# 20_FPGA_Power.net
KiCad netlist of a schematic drawn in Altium Designer
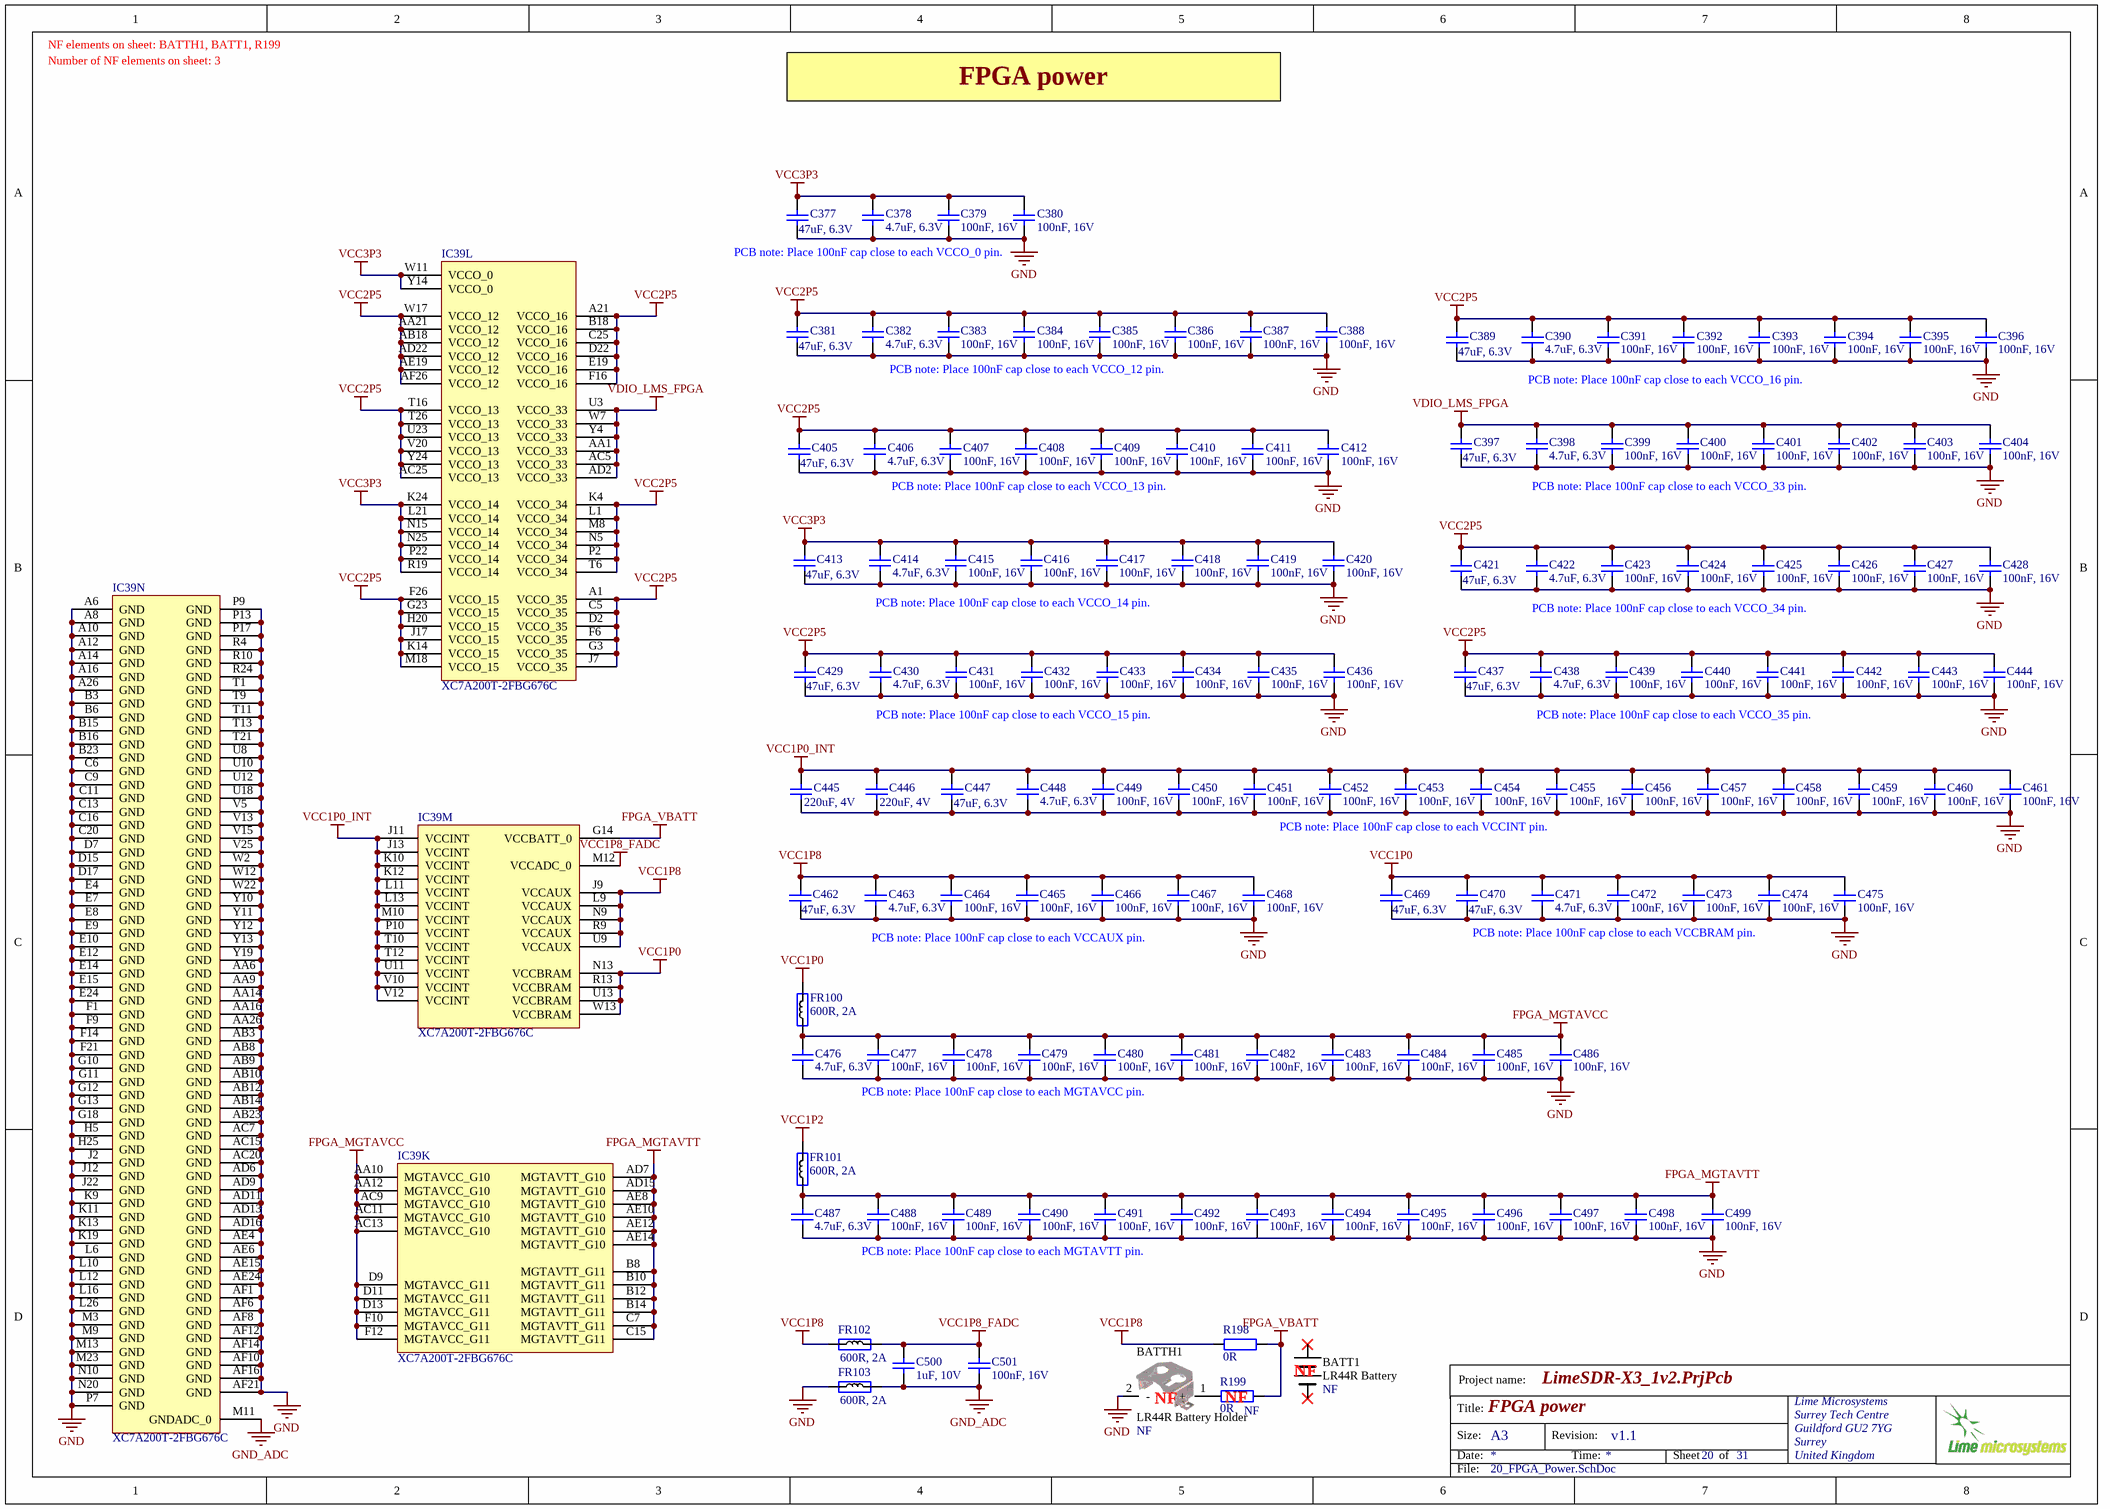
[diagram p0: 20_FPGA_Power.SchDoc]

(export (version "E")
  (design (tool "Eeschema 10.0.6"))
  (components
    (comp (ref "BATT1")
      (value "LR44R Battery")
      (fields (field (name "MANUFACTURER") "Murata") (field (name "ASSEMBLY INFO") "NF"))
      (libsource (lib "LimeMicroAltiumLib_schLib_r03") (part "LR44R_BATTERY"))
    )
    (comp (ref "BATTH1")
      (value "LR44R Battery Holder")
      (footprint "LR44R_BATTERY_HOLDER")
      (fields (field (name "MANUFACTURER") "Keystone Electronics") (field (name "ASSEMBLY INFO") "NF"))
      (libsource (lib "LimeMicroAltiumLib_schLib_r04") (part "LR44R_BATTERY_HOLDER"))
    )
    (comp (ref "C377")
      (value "47uF, 6.3V")
      (footprint "CAP1206")
      (fields
        (field (name "TOLERANCE") "±20%")
        (field (name "MANUFACTURER") "Samsung Electro-Mechanics")
        (field (name "MANUFACTURER PART NUMBER") "CL31A476MQHNNNE")
      )
      (libsource (lib "") (part "Cap_1206_1"))
    )
    (comp (ref "C378")
      (value "4.7uF, 6.3V")
      (footprint "CAP0402")
      (fields
        (field (name "MANUFACTURER") "Murata Electronics North America")
        (field (name "TOLERANCE") "±20%")
      )
      (libsource (lib "LimeMicroAltiumLib_schLib") (part "Cap_0402"))
    )
    (comp (ref "C379")
      (value "100nF, 16V")
      (footprint "CAP0402")
      (fields (field (name "MANUFACTURER") "Murata Electronics") (field (name "TOLERANCE") "10 %"))
      (libsource (lib "LimeMicroAltiumLib_schLib") (part "Cap_0402"))
    )
    (comp (ref "C380")
      (value "100nF, 16V")
      (footprint "CAP0402")
      (fields (field (name "MANUFACTURER") "Murata Electronics") (field (name "TOLERANCE") "10 %"))
      (libsource (lib "LimeMicroAltiumLib_schLib") (part "Cap_0402"))
    )
    (comp (ref "C381")
      (value "47uF, 6.3V")
      (footprint "CAP1206")
      (fields
        (field (name "TOLERANCE") "±20%")
        (field (name "MANUFACTURER") "Samsung Electro-Mechanics")
        (field (name "MANUFACTURER PART NUMBER") "CL31A476MQHNNNE")
      )
      (libsource (lib "") (part "Cap_1206_1"))
    )
    (comp (ref "C382")
      (value "4.7uF, 6.3V")
      (footprint "CAP0402")
      (fields
        (field (name "MANUFACTURER") "Murata Electronics North America")
        (field (name "TOLERANCE") "±20%")
      )
      (libsource (lib "LimeMicroAltiumLib_schLib") (part "Cap_0402"))
    )
    (comp (ref "C383")
      (value "100nF, 16V")
      (footprint "CAP0402")
      (fields (field (name "MANUFACTURER") "Murata Electronics") (field (name "TOLERANCE") "10 %"))
      (libsource (lib "LimeMicroAltiumLib_schLib") (part "Cap_0402"))
    )
    (comp (ref "C384")
      (value "100nF, 16V")
      (footprint "CAP0402")
      (fields (field (name "MANUFACTURER") "Murata Electronics") (field (name "TOLERANCE") "10 %"))
      (libsource (lib "LimeMicroAltiumLib_schLib") (part "Cap_0402"))
    )
    (comp (ref "C385")
      (value "100nF, 16V")
      (footprint "CAP0402")
      (fields (field (name "MANUFACTURER") "Murata Electronics") (field (name "TOLERANCE") "10 %"))
      (libsource (lib "") (part "Cap_0402_1"))
    )
    (comp (ref "C386")
      (value "100nF, 16V")
      (footprint "CAP0402")
      (fields (field (name "MANUFACTURER") "Murata Electronics") (field (name "TOLERANCE") "10 %"))
      (libsource (lib "") (part "Cap_0402_2"))
    )
    (comp (ref "C387")
      (value "100nF, 16V")
      (footprint "CAP0402")
      (fields (field (name "MANUFACTURER") "Murata Electronics") (field (name "TOLERANCE") "10 %"))
      (libsource (lib "") (part "Cap_0402_2"))
    )
    (comp (ref "C388")
      (value "100nF, 16V")
      (footprint "CAP0402")
      (fields (field (name "MANUFACTURER") "Murata Electronics") (field (name "TOLERANCE") "10 %"))
      (libsource (lib "LimeMicroAltiumLib_schLib") (part "Cap_0402"))
    )
    (comp (ref "C389")
      (value "47uF, 6.3V")
      (footprint "CAP1206")
      (fields
        (field (name "TOLERANCE") "±20%")
        (field (name "MANUFACTURER") "Samsung Electro-Mechanics")
        (field (name "MANUFACTURER PART NUMBER") "CL31A476MQHNNNE")
      )
      (libsource (lib "") (part "Cap_1206_1"))
    )
    (comp (ref "C390")
      (value "4.7uF, 6.3V")
      (footprint "CAP0402")
      (fields
        (field (name "MANUFACTURER") "Murata Electronics North America")
        (field (name "TOLERANCE") "±20%")
      )
      (libsource (lib "LimeMicroAltiumLib_schLib") (part "Cap_0402"))
    )
    (comp (ref "C391")
      (value "100nF, 16V")
      (footprint "CAP0402")
      (fields (field (name "MANUFACTURER") "Murata Electronics") (field (name "TOLERANCE") "10 %"))
      (libsource (lib "LimeMicroAltiumLib_schLib") (part "Cap_0402"))
    )
    (comp (ref "C392")
      (value "100nF, 16V")
      (footprint "CAP0402")
      (fields (field (name "MANUFACTURER") "Murata Electronics") (field (name "TOLERANCE") "10 %"))
      (libsource (lib "LimeMicroAltiumLib_schLib") (part "Cap_0402"))
    )
    (comp (ref "C393")
      (value "100nF, 16V")
      (footprint "CAP0402")
      (fields (field (name "MANUFACTURER") "Murata Electronics") (field (name "TOLERANCE") "10 %"))
      (libsource (lib "") (part "Cap_0402_1"))
    )
    (comp (ref "C394")
      (value "100nF, 16V")
      (footprint "CAP0402")
      (fields (field (name "MANUFACTURER") "Murata Electronics") (field (name "TOLERANCE") "10 %"))
      (libsource (lib "") (part "Cap_0402_2"))
    )
    (comp (ref "C395")
      (value "100nF, 16V")
      (footprint "CAP0402")
      (fields (field (name "MANUFACTURER") "Murata Electronics") (field (name "TOLERANCE") "10 %"))
      (libsource (lib "") (part "Cap_0402_2"))
    )
    (comp (ref "C396")
      (value "100nF, 16V")
      (footprint "CAP0402")
      (fields (field (name "MANUFACTURER") "Murata Electronics") (field (name "TOLERANCE") "10 %"))
      (libsource (lib "LimeMicroAltiumLib_schLib") (part "Cap_0402"))
    )
    (comp (ref "C397")
      (value "47uF, 6.3V")
      (footprint "CAP1206")
      (fields
        (field (name "TOLERANCE") "±20%")
        (field (name "MANUFACTURER") "Samsung Electro-Mechanics")
        (field (name "MANUFACTURER PART NUMBER") "CL31A476MQHNNNE")
      )
      (libsource (lib "LimeFPGAboard_schLib") (part "Cap_1206"))
    )
    (comp (ref "C398")
      (value "4.7uF, 6.3V")
      (footprint "CAP0402")
      (fields
        (field (name "MANUFACTURER") "Murata Electronics North America")
        (field (name "TOLERANCE") "±20%")
      )
      (libsource (lib "LimeMicroAltiumLib_schLib") (part "Cap_0402"))
    )
    (comp (ref "C399")
      (value "100nF, 16V")
      (footprint "CAP0402")
      (fields (field (name "MANUFACTURER") "Murata Electronics") (field (name "TOLERANCE") "10 %"))
      (libsource (lib "") (part "Cap_0402_2"))
    )
    (comp (ref "C400")
      (value "100nF, 16V")
      (footprint "CAP0402")
      (fields (field (name "MANUFACTURER") "Murata Electronics") (field (name "TOLERANCE") "10 %"))
      (libsource (lib "LimeMicroAltiumLib_schLib") (part "Cap_0402"))
    )
    (comp (ref "C401")
      (value "100nF, 16V")
      (footprint "CAP0402")
      (fields (field (name "MANUFACTURER") "Murata Electronics") (field (name "TOLERANCE") "10 %"))
      (libsource (lib "LimeMicroAltiumLib_schLib") (part "Cap_0402"))
    )
    (comp (ref "C402")
      (value "100nF, 16V")
      (footprint "CAP0402")
      (fields (field (name "MANUFACTURER") "Murata Electronics") (field (name "TOLERANCE") "10 %"))
      (libsource (lib "") (part "Cap_0402_1"))
    )
    (comp (ref "C403")
      (value "100nF, 16V")
      (footprint "CAP0402")
      (fields (field (name "MANUFACTURER") "Murata Electronics") (field (name "TOLERANCE") "10 %"))
      (libsource (lib "") (part "Cap_0402_2"))
    )
    (comp (ref "C404")
      (value "100nF, 16V")
      (footprint "CAP0402")
      (fields (field (name "MANUFACTURER") "Murata Electronics") (field (name "TOLERANCE") "10 %"))
      (libsource (lib "") (part "Cap_0402_2"))
    )
    (comp (ref "C405")
      (value "47uF, 6.3V")
      (footprint "CAP1206")
      (fields
        (field (name "TOLERANCE") "±20%")
        (field (name "MANUFACTURER") "Samsung Electro-Mechanics")
        (field (name "MANUFACTURER PART NUMBER") "CL31A476MQHNNNE")
      )
      (libsource (lib "") (part "Cap_1206_2"))
    )
    (comp (ref "C406")
      (value "4.7uF, 6.3V")
      (footprint "CAP0402")
      (fields
        (field (name "MANUFACTURER") "Murata Electronics North America")
        (field (name "TOLERANCE") "±20%")
      )
      (libsource (lib "") (part "Cap_0402_2"))
    )
    (comp (ref "C407")
      (value "100nF, 16V")
      (footprint "CAP0402")
      (fields (field (name "MANUFACTURER") "Murata Electronics") (field (name "TOLERANCE") "10 %"))
      (libsource (lib "") (part "Cap_0402_1"))
    )
    (comp (ref "C408")
      (value "100nF, 16V")
      (footprint "CAP0402")
      (fields (field (name "MANUFACTURER") "Murata Electronics") (field (name "TOLERANCE") "10 %"))
      (libsource (lib "") (part "Cap_0402_2"))
    )
    (comp (ref "C409")
      (value "100nF, 16V")
      (footprint "CAP0402")
      (fields (field (name "MANUFACTURER") "Murata Electronics") (field (name "TOLERANCE") "10 %"))
      (libsource (lib "") (part "Cap_0402_2"))
    )
    (comp (ref "C410")
      (value "100nF, 16V")
      (footprint "CAP0402")
      (fields (field (name "MANUFACTURER") "Murata Electronics") (field (name "TOLERANCE") "10 %"))
      (libsource (lib "LimeMicroAltiumLib_schLib") (part "Cap_0402"))
    )
    (comp (ref "C411")
      (value "100nF, 16V")
      (footprint "CAP0402")
      (fields (field (name "MANUFACTURER") "Murata Electronics") (field (name "TOLERANCE") "10 %"))
      (libsource (lib "LimeMicroAltiumLib_schLib") (part "Cap_0402"))
    )
    (comp (ref "C412")
      (value "100nF, 16V")
      (footprint "CAP0402")
      (fields (field (name "MANUFACTURER") "Murata Electronics") (field (name "TOLERANCE") "10 %"))
      (libsource (lib "") (part "Cap_0402_1"))
    )
    (comp (ref "C413")
      (value "47uF, 6.3V")
      (footprint "CAP1206")
      (fields
        (field (name "TOLERANCE") "±20%")
        (field (name "MANUFACTURER") "Samsung Electro-Mechanics")
        (field (name "MANUFACTURER PART NUMBER") "CL31A476MQHNNNE")
      )
      (libsource (lib "") (part "Cap_1206_2"))
    )
    (comp (ref "C414")
      (value "4.7uF, 6.3V")
      (footprint "CAP0402")
      (fields
        (field (name "MANUFACTURER") "Murata Electronics North America")
        (field (name "TOLERANCE") "±20%")
      )
      (libsource (lib "") (part "Cap_0402_2"))
    )
    (comp (ref "C415")
      (value "100nF, 16V")
      (footprint "CAP0402")
      (fields (field (name "MANUFACTURER") "Murata Electronics") (field (name "TOLERANCE") "10 %"))
      (libsource (lib "") (part "Cap_0402_1"))
    )
    (comp (ref "C416")
      (value "100nF, 16V")
      (footprint "CAP0402")
      (fields (field (name "MANUFACTURER") "Murata Electronics") (field (name "TOLERANCE") "10 %"))
      (libsource (lib "") (part "Cap_0402_2"))
    )
    (comp (ref "C417")
      (value "100nF, 16V")
      (footprint "CAP0402")
      (fields (field (name "MANUFACTURER") "Murata Electronics") (field (name "TOLERANCE") "10 %"))
      (libsource (lib "") (part "Cap_0402_2"))
    )
    (comp (ref "C418")
      (value "100nF, 16V")
      (footprint "CAP0402")
      (fields (field (name "MANUFACTURER") "Murata Electronics") (field (name "TOLERANCE") "10 %"))
      (libsource (lib "LimeMicroAltiumLib_schLib") (part "Cap_0402"))
    )
    (comp (ref "C419")
      (value "100nF, 16V")
      (footprint "CAP0402")
      (fields (field (name "MANUFACTURER") "Murata Electronics") (field (name "TOLERANCE") "10 %"))
      (libsource (lib "LimeMicroAltiumLib_schLib") (part "Cap_0402"))
    )
    (comp (ref "C420")
      (value "100nF, 16V")
      (footprint "CAP0402")
      (fields (field (name "MANUFACTURER") "Murata Electronics") (field (name "TOLERANCE") "10 %"))
      (libsource (lib "") (part "Cap_0402_1"))
    )
    (comp (ref "C421")
      (value "47uF, 6.3V")
      (footprint "CAP1206")
      (fields
        (field (name "TOLERANCE") "±20%")
        (field (name "MANUFACTURER") "Samsung Electro-Mechanics")
        (field (name "MANUFACTURER PART NUMBER") "CL31A476MQHNNNE")
      )
      (libsource (lib "LimeFPGAboard_schLib") (part "Cap_1206"))
    )
    (comp (ref "C422")
      (value "4.7uF, 6.3V")
      (footprint "CAP0402")
      (fields
        (field (name "MANUFACTURER") "Murata Electronics North America")
        (field (name "TOLERANCE") "±20%")
      )
      (libsource (lib "LimeMicroAltiumLib_schLib") (part "Cap_0402"))
    )
    (comp (ref "C423")
      (value "100nF, 16V")
      (footprint "CAP0402")
      (fields (field (name "MANUFACTURER") "Murata Electronics") (field (name "TOLERANCE") "10 %"))
      (libsource (lib "") (part "Cap_0402_2"))
    )
    (comp (ref "C424")
      (value "100nF, 16V")
      (footprint "CAP0402")
      (fields (field (name "MANUFACTURER") "Murata Electronics") (field (name "TOLERANCE") "10 %"))
      (libsource (lib "LimeMicroAltiumLib_schLib") (part "Cap_0402"))
    )
    (comp (ref "C425")
      (value "100nF, 16V")
      (footprint "CAP0402")
      (fields (field (name "MANUFACTURER") "Murata Electronics") (field (name "TOLERANCE") "10 %"))
      (libsource (lib "LimeMicroAltiumLib_schLib") (part "Cap_0402"))
    )
    (comp (ref "C426")
      (value "100nF, 16V")
      (footprint "CAP0402")
      (fields (field (name "MANUFACTURER") "Murata Electronics") (field (name "TOLERANCE") "10 %"))
      (libsource (lib "") (part "Cap_0402_1"))
    )
    (comp (ref "C427")
      (value "100nF, 16V")
      (footprint "CAP0402")
      (fields (field (name "MANUFACTURER") "Murata Electronics") (field (name "TOLERANCE") "10 %"))
      (libsource (lib "") (part "Cap_0402_2"))
    )
    (comp (ref "C428")
      (value "100nF, 16V")
      (footprint "CAP0402")
      (fields (field (name "MANUFACTURER") "Murata Electronics") (field (name "TOLERANCE") "10 %"))
      (libsource (lib "") (part "Cap_0402_2"))
    )
    (comp (ref "C429")
      (value "47uF, 6.3V")
      (footprint "CAP1206")
      (fields
        (field (name "TOLERANCE") "±20%")
        (field (name "MANUFACTURER") "Samsung Electro-Mechanics")
        (field (name "MANUFACTURER PART NUMBER") "CL31A476MQHNNNE")
      )
      (libsource (lib "") (part "Cap_1206_2"))
    )
    (comp (ref "C430")
      (value "4.7uF, 6.3V")
      (footprint "CAP0402")
      (fields
        (field (name "MANUFACTURER") "Murata Electronics North America")
        (field (name "TOLERANCE") "±20%")
      )
      (libsource (lib "") (part "Cap_0402_2"))
    )
    (comp (ref "C431")
      (value "100nF, 16V")
      (footprint "CAP0402")
      (fields (field (name "MANUFACTURER") "Murata Electronics") (field (name "TOLERANCE") "10 %"))
      (libsource (lib "") (part "Cap_0402_1"))
    )
    (comp (ref "C432")
      (value "100nF, 16V")
      (footprint "CAP0402")
      (fields (field (name "MANUFACTURER") "Murata Electronics") (field (name "TOLERANCE") "10 %"))
      (libsource (lib "") (part "Cap_0402_2"))
    )
    (comp (ref "C433")
      (value "100nF, 16V")
      (footprint "CAP0402")
      (fields (field (name "MANUFACTURER") "Murata Electronics") (field (name "TOLERANCE") "10 %"))
      (libsource (lib "") (part "Cap_0402_2"))
    )
    (comp (ref "C434")
      (value "100nF, 16V")
      (footprint "CAP0402")
      (fields (field (name "MANUFACTURER") "Murata Electronics") (field (name "TOLERANCE") "10 %"))
      (libsource (lib "LimeMicroAltiumLib_schLib") (part "Cap_0402"))
    )
    (comp (ref "C435")
      (value "100nF, 16V")
      (footprint "CAP0402")
      (fields (field (name "MANUFACTURER") "Murata Electronics") (field (name "TOLERANCE") "10 %"))
      (libsource (lib "LimeMicroAltiumLib_schLib") (part "Cap_0402"))
    )
    (comp (ref "C436")
      (value "100nF, 16V")
      (footprint "CAP0402")
      (fields (field (name "MANUFACTURER") "Murata Electronics") (field (name "TOLERANCE") "10 %"))
      (libsource (lib "") (part "Cap_0402_1"))
    )
    (comp (ref "C437")
      (value "47uF, 6.3V")
      (footprint "CAP1206")
      (fields
        (field (name "TOLERANCE") "±20%")
        (field (name "MANUFACTURER") "Samsung Electro-Mechanics")
        (field (name "MANUFACTURER PART NUMBER") "CL31A476MQHNNNE")
      )
      (libsource (lib "") (part "Cap_1206_2"))
    )
    (comp (ref "C438")
      (value "4.7uF, 6.3V")
      (footprint "CAP0402")
      (fields
        (field (name "MANUFACTURER") "Murata Electronics North America")
        (field (name "TOLERANCE") "±20%")
      )
      (libsource (lib "") (part "Cap_0402_1"))
    )
    (comp (ref "C439")
      (value "100nF, 16V")
      (footprint "CAP0402")
      (fields (field (name "MANUFACTURER") "Murata Electronics") (field (name "TOLERANCE") "10 %"))
      (libsource (lib "") (part "Cap_0402_2"))
    )
    (comp (ref "C440")
      (value "100nF, 16V")
      (footprint "CAP0402")
      (fields (field (name "MANUFACTURER") "Murata Electronics") (field (name "TOLERANCE") "10 %"))
      (libsource (lib "") (part "Cap_0402_2"))
    )
    (comp (ref "C441")
      (value "100nF, 16V")
      (footprint "CAP0402")
      (fields (field (name "MANUFACTURER") "Murata Electronics") (field (name "TOLERANCE") "10 %"))
      (libsource (lib "LimeMicroAltiumLib_schLib") (part "Cap_0402"))
    )
    (comp (ref "C442")
      (value "100nF, 16V")
      (footprint "CAP0402")
      (fields (field (name "MANUFACTURER") "Murata Electronics") (field (name "TOLERANCE") "10 %"))
      (libsource (lib "LimeMicroAltiumLib_schLib") (part "Cap_0402"))
    )
    (comp (ref "C443")
      (value "100nF, 16V")
      (footprint "CAP0402")
      (fields (field (name "MANUFACTURER") "Murata Electronics") (field (name "TOLERANCE") "10 %"))
      (libsource (lib "") (part "Cap_0402_1"))
    )
    (comp (ref "C444")
      (value "100nF, 16V")
      (footprint "CAP0402")
      (fields (field (name "MANUFACTURER") "Murata Electronics") (field (name "TOLERANCE") "10 %"))
      (libsource (lib "") (part "Cap_0402_2"))
    )
    (comp (ref "C445")
      (value "220uF, 4V")
      (footprint "CAP1206")
      (fields
        (field (name "MANUFACTURER") "Murata Electronics North America")
        (field (name "TOLERANCE") "±20%")
      )
      (libsource (lib "LimeFPGAboard_schLib") (part "Cap_1206"))
    )
    (comp (ref "C446")
      (value "220uF, 4V")
      (footprint "CAP1206")
      (fields
        (field (name "MANUFACTURER") "Murata Electronics North America")
        (field (name "TOLERANCE") "±20%")
      )
      (libsource (lib "") (part "Cap_1206_1"))
    )
    (comp (ref "C447")
      (value "47uF, 6.3V")
      (footprint "CAP1206")
      (fields
        (field (name "TOLERANCE") "±20%")
        (field (name "MANUFACTURER") "Samsung Electro-Mechanics")
        (field (name "MANUFACTURER PART NUMBER") "CL31A476MQHNNNE")
      )
      (libsource (lib "") (part "Cap_1206_1"))
    )
    (comp (ref "C448")
      (value "4.7uF, 6.3V")
      (footprint "CAP0402")
      (fields
        (field (name "MANUFACTURER") "Murata Electronics North America")
        (field (name "TOLERANCE") "±20%")
      )
      (libsource (lib "") (part "Cap_0402_2"))
    )
    (comp (ref "C449")
      (value "100nF, 16V")
      (footprint "CAP0402")
      (fields (field (name "MANUFACTURER") "Murata Electronics") (field (name "TOLERANCE") "10 %"))
      (libsource (lib "LimeMicroAltiumLib_schLib") (part "Cap_0402"))
    )
    (comp (ref "C450")
      (value "100nF, 16V")
      (footprint "CAP0402")
      (fields (field (name "MANUFACTURER") "Murata Electronics") (field (name "TOLERANCE") "10 %"))
      (libsource (lib "") (part "Cap_0402_1"))
    )
    (comp (ref "C451")
      (value "100nF, 16V")
      (footprint "CAP0402")
      (fields (field (name "MANUFACTURER") "Murata Electronics") (field (name "TOLERANCE") "10 %"))
      (libsource (lib "") (part "Cap_0402_2"))
    )
    (comp (ref "C452")
      (value "100nF, 16V")
      (footprint "CAP0402")
      (fields (field (name "MANUFACTURER") "Murata Electronics") (field (name "TOLERANCE") "10 %"))
      (libsource (lib "") (part "Cap_0402_2"))
    )
    (comp (ref "C453")
      (value "100nF, 16V")
      (footprint "CAP0402")
      (fields (field (name "MANUFACTURER") "Murata Electronics") (field (name "TOLERANCE") "10 %"))
      (libsource (lib "LimeMicroAltiumLib_schLib") (part "Cap_0402"))
    )
    (comp (ref "C454")
      (value "100nF, 16V")
      (footprint "CAP0402")
      (fields (field (name "MANUFACTURER") "Murata Electronics") (field (name "TOLERANCE") "10 %"))
      (libsource (lib "LimeMicroAltiumLib_schLib") (part "Cap_0402"))
    )
    (comp (ref "C455")
      (value "100nF, 16V")
      (footprint "CAP0402")
      (fields (field (name "MANUFACTURER") "Murata Electronics") (field (name "TOLERANCE") "10 %"))
      (libsource (lib "") (part "Cap_0402_1"))
    )
    (comp (ref "C456")
      (value "100nF, 16V")
      (footprint "CAP0402")
      (fields (field (name "MANUFACTURER") "Murata Electronics") (field (name "TOLERANCE") "10 %"))
      (libsource (lib "") (part "Cap_0402_2"))
    )
    (comp (ref "C457")
      (value "100nF, 16V")
      (footprint "CAP0402")
      (fields (field (name "MANUFACTURER") "Murata Electronics") (field (name "TOLERANCE") "10 %"))
      (libsource (lib "") (part "Cap_0402_2"))
    )
    (comp (ref "C458")
      (value "100nF, 16V")
      (footprint "CAP0402")
      (fields (field (name "MANUFACTURER") "Murata Electronics") (field (name "TOLERANCE") "10 %"))
      (libsource (lib "LimeMicroAltiumLib_schLib") (part "Cap_0402"))
    )
    (comp (ref "C459")
      (value "100nF, 16V")
      (footprint "CAP0402")
      (fields (field (name "MANUFACTURER") "Murata Electronics") (field (name "TOLERANCE") "10 %"))
      (libsource (lib "LimeMicroAltiumLib_schLib") (part "Cap_0402"))
    )
    (comp (ref "C460")
      (value "100nF, 16V")
      (footprint "CAP0402")
      (fields (field (name "MANUFACTURER") "Murata Electronics") (field (name "TOLERANCE") "10 %"))
      (libsource (lib "") (part "Cap_0402_1"))
    )
    (comp (ref "C461")
      (value "100nF, 16V")
      (footprint "CAP0402")
      (fields (field (name "MANUFACTURER") "Murata Electronics") (field (name "TOLERANCE") "10 %"))
      (libsource (lib "") (part "Cap_0402_2"))
    )
    (comp (ref "C462")
      (value "47uF, 6.3V")
      (footprint "CAP1206")
      (fields
        (field (name "TOLERANCE") "±20%")
        (field (name "MANUFACTURER") "Samsung Electro-Mechanics")
        (field (name "MANUFACTURER PART NUMBER") "CL31A476MQHNNNE")
      )
      (libsource (lib "") (part "Cap_1206_2"))
    )
    (comp (ref "C463")
      (value "4.7uF, 6.3V")
      (footprint "CAP0402")
      (fields
        (field (name "MANUFACTURER") "Murata Electronics North America")
        (field (name "TOLERANCE") "±20%")
      )
      (libsource (lib "") (part "Cap_0402_2"))
    )
    (comp (ref "C464")
      (value "100nF, 16V")
      (footprint "CAP0402")
      (fields (field (name "MANUFACTURER") "Murata Electronics") (field (name "TOLERANCE") "10 %"))
      (libsource (lib "") (part "Cap_0402_1"))
    )
    (comp (ref "C465")
      (value "100nF, 16V")
      (footprint "CAP0402")
      (fields (field (name "MANUFACTURER") "Murata Electronics") (field (name "TOLERANCE") "10 %"))
      (libsource (lib "") (part "Cap_0402_2"))
    )
    (comp (ref "C466")
      (value "100nF, 16V")
      (footprint "CAP0402")
      (fields (field (name "MANUFACTURER") "Murata Electronics") (field (name "TOLERANCE") "10 %"))
      (libsource (lib "") (part "Cap_0402_2"))
    )
    (comp (ref "C467")
      (value "100nF, 16V")
      (footprint "CAP0402")
      (fields (field (name "MANUFACTURER") "Murata Electronics") (field (name "TOLERANCE") "10 %"))
      (libsource (lib "LimeMicroAltiumLib_schLib") (part "Cap_0402"))
    )
    (comp (ref "C468")
      (value "100nF, 16V")
      (footprint "CAP0402")
      (fields (field (name "MANUFACTURER") "Murata Electronics") (field (name "TOLERANCE") "10 %"))
      (libsource (lib "LimeMicroAltiumLib_schLib") (part "Cap_0402"))
    )
    (comp (ref "C469")
      (value "47uF, 6.3V")
      (footprint "CAP1206")
      (fields
        (field (name "TOLERANCE") "±20%")
        (field (name "MANUFACTURER") "Samsung Electro-Mechanics")
        (field (name "MANUFACTURER PART NUMBER") "CL31A476MQHNNNE")
      )
      (libsource (lib "") (part "Cap_1206_2"))
    )
    (comp (ref "C470")
      (value "47uF, 6.3V")
      (footprint "CAP1206")
      (fields
        (field (name "TOLERANCE") "±20%")
        (field (name "MANUFACTURER") "Samsung Electro-Mechanics")
        (field (name "MANUFACTURER PART NUMBER") "CL31A476MQHNNNE")
      )
      (libsource (lib "LimeFPGAboard_schLib") (part "Cap_1206"))
    )
    (comp (ref "C471")
      (value "4.7uF, 6.3V")
      (footprint "CAP0402")
      (fields
        (field (name "MANUFACTURER") "Murata Electronics North America")
        (field (name "TOLERANCE") "±20%")
      )
      (libsource (lib "LimeMicroAltiumLib_schLib") (part "Cap_0402"))
    )
    (comp (ref "C472")
      (value "100nF, 16V")
      (footprint "CAP0402")
      (fields (field (name "MANUFACTURER") "Murata Electronics") (field (name "TOLERANCE") "10 %"))
      (libsource (lib "") (part "Cap_0402_2"))
    )
    (comp (ref "C473")
      (value "100nF, 16V")
      (footprint "CAP0402")
      (fields (field (name "MANUFACTURER") "Murata Electronics") (field (name "TOLERANCE") "10 %"))
      (libsource (lib "LimeMicroAltiumLib_schLib") (part "Cap_0402"))
    )
    (comp (ref "C474")
      (value "100nF, 16V")
      (footprint "CAP0402")
      (fields (field (name "MANUFACTURER") "Murata Electronics") (field (name "TOLERANCE") "10 %"))
      (libsource (lib "LimeMicroAltiumLib_schLib") (part "Cap_0402"))
    )
    (comp (ref "C475")
      (value "100nF, 16V")
      (footprint "CAP0402")
      (fields (field (name "MANUFACTURER") "Murata Electronics") (field (name "TOLERANCE") "10 %"))
      (libsource (lib "LimeMicroAltiumLib_schLib") (part "Cap_0402"))
    )
    (comp (ref "C476")
      (value "4.7uF, 6.3V")
      (footprint "CAP0402")
      (fields
        (field (name "MANUFACTURER") "Murata Electronics North America")
        (field (name "TOLERANCE") "±20%")
      )
      (libsource (lib "") (part "Cap_0402_1"))
    )
    (comp (ref "C477")
      (value "100nF, 16V")
      (footprint "CAP0402")
      (fields (field (name "MANUFACTURER") "Murata Electronics") (field (name "TOLERANCE") "10 %"))
      (libsource (lib "") (part "Cap_0402_2"))
    )
    (comp (ref "C478")
      (value "100nF, 16V")
      (footprint "CAP0402")
      (fields (field (name "MANUFACTURER") "Murata Electronics") (field (name "TOLERANCE") "10 %"))
      (libsource (lib "") (part "Cap_0402_2"))
    )
    (comp (ref "C479")
      (value "100nF, 16V")
      (footprint "CAP0402")
      (fields (field (name "MANUFACTURER") "Murata Electronics") (field (name "TOLERANCE") "10 %"))
      (libsource (lib "LimeMicroAltiumLib_schLib") (part "Cap_0402"))
    )
    (comp (ref "C480")
      (value "100nF, 16V")
      (footprint "CAP0402")
      (fields (field (name "MANUFACTURER") "Murata Electronics") (field (name "TOLERANCE") "10 %"))
      (libsource (lib "LimeMicroAltiumLib_schLib") (part "Cap_0402"))
    )
    (comp (ref "C481")
      (value "100nF, 16V")
      (footprint "CAP0402")
      (fields (field (name "MANUFACTURER") "Murata Electronics") (field (name "TOLERANCE") "10 %"))
      (libsource (lib "") (part "Cap_0402_3"))
    )
    (comp (ref "C482")
      (value "100nF, 16V")
      (footprint "CAP0402")
      (fields (field (name "MANUFACTURER") "Murata Electronics") (field (name "TOLERANCE") "10 %"))
      (libsource (lib "") (part "Cap_0402_2"))
    )
    (comp (ref "C483")
      (value "100nF, 16V")
      (footprint "CAP0402")
      (fields (field (name "MANUFACTURER") "Murata Electronics") (field (name "TOLERANCE") "10 %"))
      (libsource (lib "") (part "Cap_0402_2"))
    )
    (comp (ref "C484")
      (value "100nF, 16V")
      (footprint "CAP0402")
      (fields (field (name "MANUFACTURER") "Murata Electronics") (field (name "TOLERANCE") "10 %"))
      (libsource (lib "LimeMicroAltiumLib_schLib") (part "Cap_0402"))
    )
    (comp (ref "C485")
      (value "100nF, 16V")
      (footprint "CAP0402")
      (fields (field (name "MANUFACTURER") "Murata Electronics") (field (name "TOLERANCE") "10 %"))
      (libsource (lib "LimeMicroAltiumLib_schLib") (part "Cap_0402"))
    )
    (comp (ref "C486")
      (value "100nF, 16V")
      (footprint "CAP0402")
      (fields (field (name "MANUFACTURER") "Murata Electronics") (field (name "TOLERANCE") "10 %"))
      (libsource (lib "") (part "Cap_0402_3"))
    )
    (comp (ref "C487")
      (value "4.7uF, 6.3V")
      (footprint "CAP0402")
      (fields
        (field (name "MANUFACTURER") "Murata Electronics North America")
        (field (name "TOLERANCE") "±20%")
      )
      (libsource (lib "") (part "Cap_0402_2"))
    )
    (comp (ref "C488")
      (value "100nF, 16V")
      (footprint "CAP0402")
      (fields (field (name "MANUFACTURER") "Murata Electronics") (field (name "TOLERANCE") "10 %"))
      (libsource (lib "") (part "Cap_0402_2"))
    )
    (comp (ref "C489")
      (value "100nF, 16V")
      (footprint "CAP0402")
      (fields (field (name "MANUFACTURER") "Murata Electronics") (field (name "TOLERANCE") "10 %"))
      (libsource (lib "LimeMicroAltiumLib_schLib") (part "Cap_0402"))
    )
    (comp (ref "C490")
      (value "100nF, 16V")
      (footprint "CAP0402")
      (fields (field (name "MANUFACTURER") "Murata Electronics") (field (name "TOLERANCE") "10 %"))
      (libsource (lib "LimeMicroAltiumLib_schLib") (part "Cap_0402"))
    )
    (comp (ref "C491")
      (value "100nF, 16V")
      (footprint "CAP0402")
      (fields (field (name "MANUFACTURER") "Murata Electronics") (field (name "TOLERANCE") "10 %"))
      (libsource (lib "") (part "Cap_0402_1"))
    )
    (comp (ref "C492")
      (value "100nF, 16V")
      (footprint "CAP0402")
      (fields (field (name "MANUFACTURER") "Murata Electronics") (field (name "TOLERANCE") "10 %"))
      (libsource (lib "") (part "Cap_0402_2"))
    )
    (comp (ref "C493")
      (value "100nF, 16V")
      (footprint "CAP0402")
      (fields (field (name "MANUFACTURER") "Murata Electronics") (field (name "TOLERANCE") "10 %"))
      (libsource (lib "") (part "Cap_0402_2"))
    )
    (comp (ref "C494")
      (value "100nF, 16V")
      (footprint "CAP0402")
      (fields (field (name "MANUFACTURER") "Murata Electronics") (field (name "TOLERANCE") "10 %"))
      (libsource (lib "") (part "Cap_0402_2"))
    )
    (comp (ref "C495")
      (value "100nF, 16V")
      (footprint "CAP0402")
      (fields (field (name "MANUFACTURER") "Murata Electronics") (field (name "TOLERANCE") "10 %"))
      (libsource (lib "LimeMicroAltiumLib_schLib") (part "Cap_0402"))
    )
    (comp (ref "C496")
      (value "100nF, 16V")
      (footprint "CAP0402")
      (fields (field (name "MANUFACTURER") "Murata Electronics") (field (name "TOLERANCE") "10 %"))
      (libsource (lib "LimeMicroAltiumLib_schLib") (part "Cap_0402"))
    )
    (comp (ref "C497")
      (value "100nF, 16V")
      (footprint "CAP0402")
      (fields (field (name "MANUFACTURER") "Murata Electronics") (field (name "TOLERANCE") "10 %"))
      (libsource (lib "") (part "Cap_0402_3"))
    )
    (comp (ref "C498")
      (value "100nF, 16V")
      (footprint "CAP0402")
      (fields (field (name "MANUFACTURER") "Murata Electronics") (field (name "TOLERANCE") "10 %"))
      (libsource (lib "LimeMicroAltiumLib_schLib") (part "Cap_0402"))
    )
    (comp (ref "C499")
      (value "100nF, 16V")
      (footprint "CAP0402")
      (fields (field (name "MANUFACTURER") "Murata Electronics") (field (name "TOLERANCE") "10 %"))
      (libsource (lib "") (part "Cap_0402_3"))
    )
    (comp (ref "C500")
      (value "1uF, 10V")
      (footprint "CAP0402")
      (fields (field (name "MANUFACTURER") "TDK"))
      (libsource (lib "") (part "Cap_0402_1"))
    )
    (comp (ref "C501")
      (value "100nF, 16V")
      (footprint "CAP0402")
      (fields (field (name "MANUFACTURER") "Murata Electronics") (field (name "TOLERANCE") "10 %"))
      (libsource (lib "") (part "Cap_0402_2"))
    )
    (comp (ref "FR100")
      (value "600R, 2A")
      (footprint "RES0805")
      (fields (field (name "MANUFACTURER") "TDK Corporation"))
      (libsource (lib "LimeMicroAltiumLib_schLib") (part "Ferrite"))
    )
    (comp (ref "FR101")
      (value "600R, 2A")
      (footprint "RES0805")
      (fields (field (name "MANUFACTURER") "TDK Corporation"))
      (libsource (lib "LimeMicroAltiumLib_schLib") (part "Ferrite"))
    )
    (comp (ref "FR102")
      (value "600R, 2A")
      (footprint "RES0805")
      (fields (field (name "MANUFACTURER") "TDK Corporation"))
      (libsource (lib "LimeMicroAltiumLib_schLib") (part "Ferrite"))
    )
    (comp (ref "FR103")
      (value "600R, 2A")
      (footprint "RES0805")
      (fields (field (name "MANUFACTURER") "TDK Corporation"))
      (libsource (lib "LimeMicroAltiumLib_schLib") (part "Ferrite"))
    )
    (comp (ref "IC39")
      (value "XC7A200T-2FBG676C")
      (footprint "XC7A200T-2FBG676C_FBG676")
      (description "Artix-7 FPGA, 400 User I/Os, 8 GTP, 676-Ball BGA, Speed Grade 2, Commercial Grade, Pb-Free")
      (fields (field (name "MANUFACTURER") "Xilinx"))
      (libsource (lib "") (part "XC7A200T-2FBG676C_3"))
    )
    (comp (ref "R198")
      (value "0R")
      (footprint "RES0402")
      (fields (field (name "MANUFACTURER") "Yageo") (field (name "TOLERANCE") "Jumper"))
      (libsource (lib "LimeMicroAltiumLib_schLib") (part "Res_0402"))
    )
    (comp (ref "R199")
      (value "0R")
      (footprint "RES0402")
      (fields
        (field (name "ASSEMBLY INFO") "NF")
        (field (name "MANUFACTURER") "Yageo")
        (field (name "TOLERANCE") "Jumper")
      )
      (libsource (lib "LimeMicroAltiumLib_schLib") (part "Res_0402"))
    )
  )
  (nets
    (net (code "1") (name "FPGA_MGTAVCC") (class "Default")
      (node (ref "C476") (pin "2") (pinfunction "2_2") (pintype "passive"))
      (node (ref "C477") (pin "1") (pinfunction "1_1") (pintype "passive"))
      (node (ref "C478") (pin "1") (pinfunction "1_1") (pintype "passive"))
      (node (ref "C479") (pin "1") (pinfunction "1_1") (pintype "passive"))
      (node (ref "C480") (pin "1") (pinfunction "1_1") (pintype "passive"))
      (node (ref "C481") (pin "1") (pinfunction "1_1") (pintype "passive"))
      (node (ref "C482") (pin "1") (pinfunction "1_1") (pintype "passive"))
      (node (ref "C483") (pin "1") (pinfunction "1_1") (pintype "passive"))
      (node (ref "C484") (pin "1") (pinfunction "1_1") (pintype "passive"))
      (node (ref "C485") (pin "1") (pinfunction "1_1") (pintype "passive"))
      (node (ref "C486") (pin "1") (pinfunction "1_1") (pintype "passive"))
      (node (ref "FR100") (pin "1") (pinfunction "1_1") (pintype "passive"))
      (node (ref "IC39") (pin "AA10") (pinfunction "MGTAVCC_G10_AA10") (pintype "power_in"))
      (node (ref "IC39") (pin "AA12") (pinfunction "MGTAVCC_G10_AA12") (pintype "power_in"))
      (node (ref "IC39") (pin "AC11") (pinfunction "MGTAVCC_G10_AC11") (pintype "power_in"))
      (node (ref "IC39") (pin "AC13") (pinfunction "MGTAVCC_G10_AC13") (pintype "power_in"))
      (node (ref "IC39") (pin "AC9") (pinfunction "MGTAVCC_G10_AC9") (pintype "power_in"))
      (node (ref "IC39") (pin "D11") (pinfunction "MGTAVCC_G11_D11") (pintype "power_in"))
      (node (ref "IC39") (pin "D13") (pinfunction "MGTAVCC_G11_D13") (pintype "power_in"))
      (node (ref "IC39") (pin "D9") (pinfunction "MGTAVCC_G11_D9") (pintype "power_in"))
      (node (ref "IC39") (pin "F10") (pinfunction "MGTAVCC_G11_F10") (pintype "power_in"))
      (node (ref "IC39") (pin "F12") (pinfunction "MGTAVCC_G11_F12") (pintype "power_in"))
    )
    (net (code "2") (name "FPGA_MGTAVTT") (class "Default")
      (node (ref "C487") (pin "2") (pinfunction "2_2") (pintype "passive"))
      (node (ref "C488") (pin "1") (pinfunction "1_1") (pintype "passive"))
      (node (ref "C489") (pin "1") (pinfunction "1_1") (pintype "passive"))
      (node (ref "C490") (pin "1") (pinfunction "1_1") (pintype "passive"))
      (node (ref "C491") (pin "1") (pinfunction "1_1") (pintype "passive"))
      (node (ref "C492") (pin "1") (pinfunction "1_1") (pintype "passive"))
      (node (ref "C493") (pin "1") (pinfunction "1_1") (pintype "passive"))
      (node (ref "C494") (pin "1") (pinfunction "1_1") (pintype "passive"))
      (node (ref "C495") (pin "1") (pinfunction "1_1") (pintype "passive"))
      (node (ref "C496") (pin "1") (pinfunction "1_1") (pintype "passive"))
      (node (ref "C497") (pin "1") (pinfunction "1_1") (pintype "passive"))
      (node (ref "C498") (pin "1") (pinfunction "1_1") (pintype "passive"))
      (node (ref "C499") (pin "1") (pinfunction "1_1") (pintype "passive"))
      (node (ref "FR101") (pin "1") (pinfunction "1_1") (pintype "passive"))
      (node (ref "IC39") (pin "AD15") (pinfunction "MGTAVTT_G10_AD15") (pintype "power_in"))
      (node (ref "IC39") (pin "AD7") (pinfunction "MGTAVTT_G10_AD7") (pintype "power_in"))
      (node (ref "IC39") (pin "AE10") (pinfunction "MGTAVTT_G10_AE10") (pintype "power_in"))
      (node (ref "IC39") (pin "AE12") (pinfunction "MGTAVTT_G10_AE12") (pintype "power_in"))
      (node (ref "IC39") (pin "AE14") (pinfunction "MGTAVTT_G10_AE14") (pintype "power_in"))
      (node (ref "IC39") (pin "AE8") (pinfunction "MGTAVTT_G10_AE8") (pintype "power_in"))
      (node (ref "IC39") (pin "B10") (pinfunction "MGTAVTT_G11_B10") (pintype "power_in"))
      (node (ref "IC39") (pin "B12") (pinfunction "MGTAVTT_G11_B12") (pintype "power_in"))
      (node (ref "IC39") (pin "B14") (pinfunction "MGTAVTT_G11_B14") (pintype "power_in"))
      (node (ref "IC39") (pin "B8") (pinfunction "MGTAVTT_G11_B8") (pintype "power_in"))
      (node (ref "IC39") (pin "C15") (pinfunction "MGTAVTT_G11_C15") (pintype "power_in"))
      (node (ref "IC39") (pin "C7") (pinfunction "MGTAVTT_G11_C7") (pintype "power_in"))
    )
    (net (code "3") (name "FPGA_VBATT") (class "Default")
      (node (ref "IC39") (pin "G14") (pinfunction "VCCBATT_0_G14") (pintype "power_in"))
      (node (ref "R198") (pin "2") (pinfunction "2_2") (pintype "passive"))
      (node (ref "R199") (pin "2") (pinfunction "2_2") (pintype "passive"))
    )
    (net (code "4") (name "GND") (class "Default")
      (node (ref "BATTH1") (pin "2") (pinfunction "-_2") (pintype "passive"))
      (node (ref "C377") (pin "1") (pinfunction "1_1") (pintype "passive"))
      (node (ref "C378") (pin "1") (pinfunction "1_1") (pintype "passive"))
      (node (ref "C379") (pin "2") (pinfunction "2_2") (pintype "passive"))
      (node (ref "C380") (pin "2") (pinfunction "2_2") (pintype "passive"))
      (node (ref "C381") (pin "1") (pinfunction "1_1") (pintype "passive"))
      (node (ref "C382") (pin "1") (pinfunction "1_1") (pintype "passive"))
      (node (ref "C383") (pin "2") (pinfunction "2_2") (pintype "passive"))
      (node (ref "C384") (pin "2") (pinfunction "2_2") (pintype "passive"))
      (node (ref "C385") (pin "2") (pinfunction "2_2") (pintype "passive"))
      (node (ref "C386") (pin "2") (pinfunction "2_2") (pintype "passive"))
      (node (ref "C387") (pin "2") (pinfunction "2_2") (pintype "passive"))
      (node (ref "C388") (pin "2") (pinfunction "2_2") (pintype "passive"))
      (node (ref "C389") (pin "1") (pinfunction "1_1") (pintype "passive"))
      (node (ref "C390") (pin "1") (pinfunction "1_1") (pintype "passive"))
      (node (ref "C391") (pin "2") (pinfunction "2_2") (pintype "passive"))
      (node (ref "C392") (pin "2") (pinfunction "2_2") (pintype "passive"))
      (node (ref "C393") (pin "2") (pinfunction "2_2") (pintype "passive"))
      (node (ref "C394") (pin "2") (pinfunction "2_2") (pintype "passive"))
      (node (ref "C395") (pin "2") (pinfunction "2_2") (pintype "passive"))
      (node (ref "C396") (pin "2") (pinfunction "2_2") (pintype "passive"))
      (node (ref "C397") (pin "1") (pinfunction "1_1") (pintype "passive"))
      (node (ref "C398") (pin "1") (pinfunction "1_1") (pintype "passive"))
      (node (ref "C399") (pin "2") (pinfunction "2_2") (pintype "passive"))
      (node (ref "C400") (pin "2") (pinfunction "2_2") (pintype "passive"))
      (node (ref "C401") (pin "2") (pinfunction "2_2") (pintype "passive"))
      (node (ref "C402") (pin "2") (pinfunction "2_2") (pintype "passive"))
      (node (ref "C403") (pin "2") (pinfunction "2_2") (pintype "passive"))
      (node (ref "C404") (pin "2") (pinfunction "2_2") (pintype "passive"))
      (node (ref "C405") (pin "1") (pinfunction "1_1") (pintype "passive"))
      (node (ref "C406") (pin "1") (pinfunction "1_1") (pintype "passive"))
      (node (ref "C407") (pin "2") (pinfunction "2_2") (pintype "passive"))
      (node (ref "C408") (pin "2") (pinfunction "2_2") (pintype "passive"))
      (node (ref "C409") (pin "2") (pinfunction "2_2") (pintype "passive"))
      (node (ref "C410") (pin "2") (pinfunction "2_2") (pintype "passive"))
      (node (ref "C411") (pin "2") (pinfunction "2_2") (pintype "passive"))
      (node (ref "C412") (pin "2") (pinfunction "2_2") (pintype "passive"))
      (node (ref "C413") (pin "1") (pinfunction "1_1") (pintype "passive"))
      (node (ref "C414") (pin "1") (pinfunction "1_1") (pintype "passive"))
      (node (ref "C415") (pin "2") (pinfunction "2_2") (pintype "passive"))
      (node (ref "C416") (pin "2") (pinfunction "2_2") (pintype "passive"))
      (node (ref "C417") (pin "2") (pinfunction "2_2") (pintype "passive"))
      (node (ref "C418") (pin "2") (pinfunction "2_2") (pintype "passive"))
      (node (ref "C419") (pin "2") (pinfunction "2_2") (pintype "passive"))
      (node (ref "C420") (pin "2") (pinfunction "2_2") (pintype "passive"))
      (node (ref "C421") (pin "1") (pinfunction "1_1") (pintype "passive"))
      (node (ref "C422") (pin "1") (pinfunction "1_1") (pintype "passive"))
      (node (ref "C423") (pin "2") (pinfunction "2_2") (pintype "passive"))
      (node (ref "C424") (pin "2") (pinfunction "2_2") (pintype "passive"))
      (node (ref "C425") (pin "2") (pinfunction "2_2") (pintype "passive"))
      (node (ref "C426") (pin "2") (pinfunction "2_2") (pintype "passive"))
      (node (ref "C427") (pin "2") (pinfunction "2_2") (pintype "passive"))
      (node (ref "C428") (pin "2") (pinfunction "2_2") (pintype "passive"))
      (node (ref "C429") (pin "1") (pinfunction "1_1") (pintype "passive"))
      (node (ref "C430") (pin "1") (pinfunction "1_1") (pintype "passive"))
      (node (ref "C431") (pin "2") (pinfunction "2_2") (pintype "passive"))
      (node (ref "C432") (pin "2") (pinfunction "2_2") (pintype "passive"))
      (node (ref "C433") (pin "2") (pinfunction "2_2") (pintype "passive"))
      (node (ref "C434") (pin "2") (pinfunction "2_2") (pintype "passive"))
      (node (ref "C435") (pin "2") (pinfunction "2_2") (pintype "passive"))
      (node (ref "C436") (pin "2") (pinfunction "2_2") (pintype "passive"))
      (node (ref "C437") (pin "1") (pinfunction "1_1") (pintype "passive"))
      (node (ref "C438") (pin "1") (pinfunction "1_1") (pintype "passive"))
      (node (ref "C439") (pin "2") (pinfunction "2_2") (pintype "passive"))
      (node (ref "C440") (pin "2") (pinfunction "2_2") (pintype "passive"))
      (node (ref "C441") (pin "2") (pinfunction "2_2") (pintype "passive"))
      (node (ref "C442") (pin "2") (pinfunction "2_2") (pintype "passive"))
      (node (ref "C443") (pin "2") (pinfunction "2_2") (pintype "passive"))
      (node (ref "C444") (pin "2") (pinfunction "2_2") (pintype "passive"))
      (node (ref "C445") (pin "1") (pinfunction "1_1") (pintype "passive"))
      (node (ref "C446") (pin "1") (pinfunction "1_1") (pintype "passive"))
      (node (ref "C447") (pin "1") (pinfunction "1_1") (pintype "passive"))
      (node (ref "C448") (pin "1") (pinfunction "1_1") (pintype "passive"))
      (node (ref "C449") (pin "2") (pinfunction "2_2") (pintype "passive"))
      (node (ref "C450") (pin "2") (pinfunction "2_2") (pintype "passive"))
      (node (ref "C451") (pin "2") (pinfunction "2_2") (pintype "passive"))
      (node (ref "C452") (pin "2") (pinfunction "2_2") (pintype "passive"))
      (node (ref "C453") (pin "2") (pinfunction "2_2") (pintype "passive"))
      (node (ref "C454") (pin "2") (pinfunction "2_2") (pintype "passive"))
      (node (ref "C455") (pin "2") (pinfunction "2_2") (pintype "passive"))
      (node (ref "C456") (pin "2") (pinfunction "2_2") (pintype "passive"))
      (node (ref "C457") (pin "2") (pinfunction "2_2") (pintype "passive"))
      (node (ref "C458") (pin "2") (pinfunction "2_2") (pintype "passive"))
      (node (ref "C459") (pin "2") (pinfunction "2_2") (pintype "passive"))
      (node (ref "C460") (pin "2") (pinfunction "2_2") (pintype "passive"))
      (node (ref "C461") (pin "2") (pinfunction "2_2") (pintype "passive"))
      (node (ref "C462") (pin "1") (pinfunction "1_1") (pintype "passive"))
      (node (ref "C463") (pin "1") (pinfunction "1_1") (pintype "passive"))
      (node (ref "C464") (pin "2") (pinfunction "2_2") (pintype "passive"))
      (node (ref "C465") (pin "2") (pinfunction "2_2") (pintype "passive"))
      (node (ref "C466") (pin "2") (pinfunction "2_2") (pintype "passive"))
      (node (ref "C467") (pin "2") (pinfunction "2_2") (pintype "passive"))
      (node (ref "C468") (pin "2") (pinfunction "2_2") (pintype "passive"))
      (node (ref "C469") (pin "1") (pinfunction "1_1") (pintype "passive"))
      (node (ref "C470") (pin "1") (pinfunction "1_1") (pintype "passive"))
      (node (ref "C471") (pin "1") (pinfunction "1_1") (pintype "passive"))
      (node (ref "C472") (pin "2") (pinfunction "2_2") (pintype "passive"))
      (node (ref "C473") (pin "2") (pinfunction "2_2") (pintype "passive"))
      (node (ref "C474") (pin "2") (pinfunction "2_2") (pintype "passive"))
      (node (ref "C475") (pin "2") (pinfunction "2_2") (pintype "passive"))
      (node (ref "C476") (pin "1") (pinfunction "1_1") (pintype "passive"))
      (node (ref "C477") (pin "2") (pinfunction "2_2") (pintype "passive"))
      (node (ref "C478") (pin "2") (pinfunction "2_2") (pintype "passive"))
      (node (ref "C479") (pin "2") (pinfunction "2_2") (pintype "passive"))
      (node (ref "C480") (pin "2") (pinfunction "2_2") (pintype "passive"))
      (node (ref "C481") (pin "2") (pinfunction "2_2") (pintype "passive"))
      (node (ref "C482") (pin "2") (pinfunction "2_2") (pintype "passive"))
      (node (ref "C483") (pin "2") (pinfunction "2_2") (pintype "passive"))
      (node (ref "C484") (pin "2") (pinfunction "2_2") (pintype "passive"))
      (node (ref "C485") (pin "2") (pinfunction "2_2") (pintype "passive"))
      (node (ref "C486") (pin "2") (pinfunction "2_2") (pintype "passive"))
      (node (ref "C487") (pin "1") (pinfunction "1_1") (pintype "passive"))
      (node (ref "C488") (pin "2") (pinfunction "2_2") (pintype "passive"))
      (node (ref "C489") (pin "2") (pinfunction "2_2") (pintype "passive"))
      (node (ref "C490") (pin "2") (pinfunction "2_2") (pintype "passive"))
      (node (ref "C491") (pin "2") (pinfunction "2_2") (pintype "passive"))
      (node (ref "C492") (pin "2") (pinfunction "2_2") (pintype "passive"))
      (node (ref "C493") (pin "2") (pinfunction "2_2") (pintype "passive"))
      (node (ref "C494") (pin "2") (pinfunction "2_2") (pintype "passive"))
      (node (ref "C495") (pin "2") (pinfunction "2_2") (pintype "passive"))
      (node (ref "C496") (pin "2") (pinfunction "2_2") (pintype "passive"))
      (node (ref "C497") (pin "2") (pinfunction "2_2") (pintype "passive"))
      (node (ref "C498") (pin "2") (pinfunction "2_2") (pintype "passive"))
      (node (ref "C499") (pin "2") (pinfunction "2_2") (pintype "passive"))
      (node (ref "FR103") (pin "1") (pinfunction "1_1") (pintype "passive"))
      (node (ref "IC39") (pin "A10") (pinfunction "GND_A10") (pintype "power_in"))
      (node (ref "IC39") (pin "A12") (pinfunction "GND_A12") (pintype "power_in"))
      (node (ref "IC39") (pin "A14") (pinfunction "GND_A14") (pintype "power_in"))
      (node (ref "IC39") (pin "A16") (pinfunction "GND_A16") (pintype "power_in"))
      (node (ref "IC39") (pin "A26") (pinfunction "GND_A26") (pintype "power_in"))
      (node (ref "IC39") (pin "A6") (pinfunction "GND_A6") (pintype "power_in"))
      (node (ref "IC39") (pin "A8") (pinfunction "GND_A8") (pintype "power_in"))
      (node (ref "IC39") (pin "AA14") (pinfunction "GND_AA14") (pintype "power_in"))
      (node (ref "IC39") (pin "AA16") (pinfunction "GND_AA16") (pintype "power_in"))
      (node (ref "IC39") (pin "AA26") (pinfunction "GND_AA26") (pintype "power_in"))
      (node (ref "IC39") (pin "AA6") (pinfunction "GND_AA6") (pintype "power_in"))
      (node (ref "IC39") (pin "AA9") (pinfunction "GND_AA9") (pintype "power_in"))
      (node (ref "IC39") (pin "AB10") (pinfunction "GND_AB10") (pintype "power_in"))
      (node (ref "IC39") (pin "AB12") (pinfunction "GND_AB12") (pintype "power_in"))
      (node (ref "IC39") (pin "AB14") (pinfunction "GND_AB14") (pintype "power_in"))
      (node (ref "IC39") (pin "AB23") (pinfunction "GND_AB23") (pintype "power_in"))
      (node (ref "IC39") (pin "AB3") (pinfunction "GND_AB3") (pintype "power_in"))
      (node (ref "IC39") (pin "AB8") (pinfunction "GND_AB8") (pintype "power_in"))
      (node (ref "IC39") (pin "AB9") (pinfunction "GND_AB9") (pintype "power_in"))
      (node (ref "IC39") (pin "AC15") (pinfunction "GND_AC15") (pintype "power_in"))
      (node (ref "IC39") (pin "AC20") (pinfunction "GND_AC20") (pintype "power_in"))
      (node (ref "IC39") (pin "AC7") (pinfunction "GND_AC7") (pintype "power_in"))
      (node (ref "IC39") (pin "AD11") (pinfunction "GND_AD11") (pintype "power_in"))
      (node (ref "IC39") (pin "AD13") (pinfunction "GND_AD13") (pintype "power_in"))
      (node (ref "IC39") (pin "AD16") (pinfunction "GND_AD16") (pintype "power_in"))
      (node (ref "IC39") (pin "AD6") (pinfunction "GND_AD6") (pintype "power_in"))
      (node (ref "IC39") (pin "AD9") (pinfunction "GND_AD9") (pintype "power_in"))
      (node (ref "IC39") (pin "AE15") (pinfunction "GND_AE15") (pintype "power_in"))
      (node (ref "IC39") (pin "AE24") (pinfunction "GND_AE24") (pintype "power_in"))
      (node (ref "IC39") (pin "AE4") (pinfunction "GND_AE4") (pintype "power_in"))
      (node (ref "IC39") (pin "AE6") (pinfunction "GND_AE6") (pintype "power_in"))
      (node (ref "IC39") (pin "AF1") (pinfunction "GND_AF1") (pintype "power_in"))
      (node (ref "IC39") (pin "AF10") (pinfunction "GND_AF10") (pintype "power_in"))
      (node (ref "IC39") (pin "AF12") (pinfunction "GND_AF12") (pintype "power_in"))
      (node (ref "IC39") (pin "AF14") (pinfunction "GND_AF14") (pintype "power_in"))
      (node (ref "IC39") (pin "AF16") (pinfunction "GND_AF16") (pintype "power_in"))
      (node (ref "IC39") (pin "AF21") (pinfunction "GND_AF21") (pintype "power_in"))
      (node (ref "IC39") (pin "AF6") (pinfunction "GND_AF6") (pintype "power_in"))
      (node (ref "IC39") (pin "AF8") (pinfunction "GND_AF8") (pintype "power_in"))
      (node (ref "IC39") (pin "B15") (pinfunction "GND_B15") (pintype "power_in"))
      (node (ref "IC39") (pin "B16") (pinfunction "GND_B16") (pintype "power_in"))
      (node (ref "IC39") (pin "B23") (pinfunction "GND_B23") (pintype "power_in"))
      (node (ref "IC39") (pin "B3") (pinfunction "GND_B3") (pintype "power_in"))
      (node (ref "IC39") (pin "B6") (pinfunction "GND_B6") (pintype "power_in"))
      (node (ref "IC39") (pin "C11") (pinfunction "GND_C11") (pintype "power_in"))
      (node (ref "IC39") (pin "C13") (pinfunction "GND_C13") (pintype "power_in"))
      (node (ref "IC39") (pin "C16") (pinfunction "GND_C16") (pintype "power_in"))
      (node (ref "IC39") (pin "C20") (pinfunction "GND_C20") (pintype "power_in"))
      (node (ref "IC39") (pin "C6") (pinfunction "GND_C6") (pintype "power_in"))
      (node (ref "IC39") (pin "C9") (pinfunction "GND_C9") (pintype "power_in"))
      (node (ref "IC39") (pin "D15") (pinfunction "GND_D15") (pintype "power_in"))
      (node (ref "IC39") (pin "D17") (pinfunction "GND_D17") (pintype "power_in"))
      (node (ref "IC39") (pin "D7") (pinfunction "GND_D7") (pintype "power_in"))
      (node (ref "IC39") (pin "E10") (pinfunction "GND_E10") (pintype "power_in"))
      (node (ref "IC39") (pin "E12") (pinfunction "GND_E12") (pintype "power_in"))
      (node (ref "IC39") (pin "E14") (pinfunction "GND_E14") (pintype "power_in"))
      (node (ref "IC39") (pin "E15") (pinfunction "GND_E15") (pintype "power_in"))
      (node (ref "IC39") (pin "E24") (pinfunction "GND_E24") (pintype "power_in"))
      (node (ref "IC39") (pin "E4") (pinfunction "GND_E4") (pintype "power_in"))
      (node (ref "IC39") (pin "E7") (pinfunction "GND_E7") (pintype "power_in"))
      (node (ref "IC39") (pin "E8") (pinfunction "GND_E8") (pintype "power_in"))
      (node (ref "IC39") (pin "E9") (pinfunction "GND_E9") (pintype "power_in"))
      (node (ref "IC39") (pin "F1") (pinfunction "GND_F1") (pintype "power_in"))
      (node (ref "IC39") (pin "F14") (pinfunction "GND_F14") (pintype "power_in"))
      (node (ref "IC39") (pin "F21") (pinfunction "GND_F21") (pintype "power_in"))
      (node (ref "IC39") (pin "F9") (pinfunction "GND_F9") (pintype "power_in"))
      (node (ref "IC39") (pin "G10") (pinfunction "GND_G10") (pintype "power_in"))
      (node (ref "IC39") (pin "G11") (pinfunction "GND_G11") (pintype "power_in"))
      (node (ref "IC39") (pin "G12") (pinfunction "GND_G12") (pintype "power_in"))
      (node (ref "IC39") (pin "G13") (pinfunction "GND_G13") (pintype "power_in"))
      (node (ref "IC39") (pin "G18") (pinfunction "GND_G18") (pintype "power_in"))
      (node (ref "IC39") (pin "H25") (pinfunction "GND_H25") (pintype "power_in"))
      (node (ref "IC39") (pin "H5") (pinfunction "GND_H5") (pintype "power_in"))
      (node (ref "IC39") (pin "J12") (pinfunction "GND_J12") (pintype "power_in"))
      (node (ref "IC39") (pin "J2") (pinfunction "GND_J2") (pintype "power_in"))
      (node (ref "IC39") (pin "J22") (pinfunction "GND_J22") (pintype "power_in"))
      (node (ref "IC39") (pin "K11") (pinfunction "GND_K11") (pintype "power_in"))
      (node (ref "IC39") (pin "K13") (pinfunction "GND_K13") (pintype "power_in"))
      (node (ref "IC39") (pin "K19") (pinfunction "GND_K19") (pintype "power_in"))
      (node (ref "IC39") (pin "K9") (pinfunction "GND_K9") (pintype "power_in"))
      (node (ref "IC39") (pin "L10") (pinfunction "GND_L10") (pintype "power_in"))
      (node (ref "IC39") (pin "L12") (pinfunction "GND_L12") (pintype "power_in"))
      (node (ref "IC39") (pin "L16") (pinfunction "GND_L16") (pintype "power_in"))
      (node (ref "IC39") (pin "L26") (pinfunction "GND_L26") (pintype "power_in"))
      (node (ref "IC39") (pin "L6") (pinfunction "GND_L6") (pintype "power_in"))
      (node (ref "IC39") (pin "M13") (pinfunction "GND_M13") (pintype "power_in"))
      (node (ref "IC39") (pin "M23") (pinfunction "GND_M23") (pintype "power_in"))
      (node (ref "IC39") (pin "M3") (pinfunction "GND_M3") (pintype "power_in"))
      (node (ref "IC39") (pin "M9") (pinfunction "GND_M9") (pintype "power_in"))
      (node (ref "IC39") (pin "N10") (pinfunction "GND_N10") (pintype "power_in"))
      (node (ref "IC39") (pin "N20") (pinfunction "GND_N20") (pintype "power_in"))
      (node (ref "IC39") (pin "P13") (pinfunction "GND_P13") (pintype "power_in"))
      (node (ref "IC39") (pin "P17") (pinfunction "GND_P17") (pintype "power_in"))
      (node (ref "IC39") (pin "P7") (pinfunction "GND_P7") (pintype "power_in"))
      (node (ref "IC39") (pin "P9") (pinfunction "GND_P9") (pintype "power_in"))
      (node (ref "IC39") (pin "R10") (pinfunction "GND_R10") (pintype "power_in"))
      (node (ref "IC39") (pin "R24") (pinfunction "GND_R24") (pintype "power_in"))
      (node (ref "IC39") (pin "R4") (pinfunction "GND_R4") (pintype "power_in"))
      (node (ref "IC39") (pin "T1") (pinfunction "GND_T1") (pintype "power_in"))
      (node (ref "IC39") (pin "T11") (pinfunction "GND_T11") (pintype "power_in"))
      (node (ref "IC39") (pin "T13") (pinfunction "GND_T13") (pintype "power_in"))
      (node (ref "IC39") (pin "T21") (pinfunction "GND_T21") (pintype "power_in"))
      (node (ref "IC39") (pin "T9") (pinfunction "GND_T9") (pintype "power_in"))
      (node (ref "IC39") (pin "U10") (pinfunction "GND_U10") (pintype "power_in"))
      (node (ref "IC39") (pin "U12") (pinfunction "GND_U12") (pintype "power_in"))
      (node (ref "IC39") (pin "U18") (pinfunction "GND_U18") (pintype "power_in"))
      (node (ref "IC39") (pin "U8") (pinfunction "GND_U8") (pintype "power_in"))
      (node (ref "IC39") (pin "V13") (pinfunction "GND_V13") (pintype "power_in"))
      (node (ref "IC39") (pin "V15") (pinfunction "GND_V15") (pintype "power_in"))
      (node (ref "IC39") (pin "V25") (pinfunction "GND_V25") (pintype "power_in"))
      (node (ref "IC39") (pin "V5") (pinfunction "GND_V5") (pintype "power_in"))
      (node (ref "IC39") (pin "W12") (pinfunction "GND_W12") (pintype "power_in"))
      (node (ref "IC39") (pin "W2") (pinfunction "GND_W2") (pintype "power_in"))
      (node (ref "IC39") (pin "W22") (pinfunction "GND_W22") (pintype "power_in"))
      (node (ref "IC39") (pin "Y10") (pinfunction "GND_Y10") (pintype "power_in"))
      (node (ref "IC39") (pin "Y11") (pinfunction "GND_Y11") (pintype "power_in"))
      (node (ref "IC39") (pin "Y12") (pinfunction "GND_Y12") (pintype "power_in"))
      (node (ref "IC39") (pin "Y13") (pinfunction "GND_Y13") (pintype "power_in"))
      (node (ref "IC39") (pin "Y19") (pinfunction "GND_Y19") (pintype "power_in"))
    )
    (net (code "5") (name "GND_ADC") (class "Default")
      (node (ref "C500") (pin "1") (pinfunction "1_1") (pintype "passive"))
      (node (ref "C501") (pin "2") (pinfunction "2_2") (pintype "passive"))
      (node (ref "FR103") (pin "2") (pinfunction "2_2") (pintype "passive"))
      (node (ref "IC39") (pin "M11") (pinfunction "GNDADC_0_M11") (pintype "power_in"))
    )
    (net (code "6") (name "Net-(BATTH1-+)") (class "Default")
      (node (ref "BATTH1") (pin "1") (pinfunction "+_1") (pintype "passive"))
      (node (ref "R199") (pin "1") (pinfunction "1_1") (pintype "passive"))
    )
    (net (code "7") (name "VCC1P0") (class "Default")
      (node (ref "C469") (pin "2") (pinfunction "2_2") (pintype "passive"))
      (node (ref "C470") (pin "2") (pinfunction "2_2") (pintype "passive"))
      (node (ref "C471") (pin "2") (pinfunction "2_2") (pintype "passive"))
      (node (ref "C472") (pin "1") (pinfunction "1_1") (pintype "passive"))
      (node (ref "C473") (pin "1") (pinfunction "1_1") (pintype "passive"))
      (node (ref "C474") (pin "1") (pinfunction "1_1") (pintype "passive"))
      (node (ref "C475") (pin "1") (pinfunction "1_1") (pintype "passive"))
      (node (ref "FR100") (pin "2") (pinfunction "2_2") (pintype "passive"))
      (node (ref "IC39") (pin "N13") (pinfunction "VCCBRAM_N13") (pintype "power_in"))
      (node (ref "IC39") (pin "R13") (pinfunction "VCCBRAM_R13") (pintype "power_in"))
      (node (ref "IC39") (pin "U13") (pinfunction "VCCBRAM_U13") (pintype "power_in"))
      (node (ref "IC39") (pin "W13") (pinfunction "VCCBRAM_W13") (pintype "power_in"))
    )
    (net (code "8") (name "VCC1P0_INT") (class "Default")
      (node (ref "C445") (pin "2") (pinfunction "2_2") (pintype "passive"))
      (node (ref "C446") (pin "2") (pinfunction "2_2") (pintype "passive"))
      (node (ref "C447") (pin "2") (pinfunction "2_2") (pintype "passive"))
      (node (ref "C448") (pin "2") (pinfunction "2_2") (pintype "passive"))
      (node (ref "C449") (pin "1") (pinfunction "1_1") (pintype "passive"))
      (node (ref "C450") (pin "1") (pinfunction "1_1") (pintype "passive"))
      (node (ref "C451") (pin "1") (pinfunction "1_1") (pintype "passive"))
      (node (ref "C452") (pin "1") (pinfunction "1_1") (pintype "passive"))
      (node (ref "C453") (pin "1") (pinfunction "1_1") (pintype "passive"))
      (node (ref "C454") (pin "1") (pinfunction "1_1") (pintype "passive"))
      (node (ref "C455") (pin "1") (pinfunction "1_1") (pintype "passive"))
      (node (ref "C456") (pin "1") (pinfunction "1_1") (pintype "passive"))
      (node (ref "C457") (pin "1") (pinfunction "1_1") (pintype "passive"))
      (node (ref "C458") (pin "1") (pinfunction "1_1") (pintype "passive"))
      (node (ref "C459") (pin "1") (pinfunction "1_1") (pintype "passive"))
      (node (ref "C460") (pin "1") (pinfunction "1_1") (pintype "passive"))
      (node (ref "C461") (pin "1") (pinfunction "1_1") (pintype "passive"))
      (node (ref "IC39") (pin "J11") (pinfunction "VCCINT_J11") (pintype "power_in"))
      (node (ref "IC39") (pin "J13") (pinfunction "VCCINT_J13") (pintype "power_in"))
      (node (ref "IC39") (pin "K10") (pinfunction "VCCINT_K10") (pintype "power_in"))
      (node (ref "IC39") (pin "K12") (pinfunction "VCCINT_K12") (pintype "power_in"))
      (node (ref "IC39") (pin "L11") (pinfunction "VCCINT_L11") (pintype "power_in"))
      (node (ref "IC39") (pin "L13") (pinfunction "VCCINT_L13") (pintype "power_in"))
      (node (ref "IC39") (pin "M10") (pinfunction "VCCINT_M10") (pintype "power_in"))
      (node (ref "IC39") (pin "P10") (pinfunction "VCCINT_P10") (pintype "power_in"))
      (node (ref "IC39") (pin "T10") (pinfunction "VCCINT_T10") (pintype "power_in"))
      (node (ref "IC39") (pin "T12") (pinfunction "VCCINT_T12") (pintype "power_in"))
      (node (ref "IC39") (pin "U11") (pinfunction "VCCINT_U11") (pintype "power_in"))
      (node (ref "IC39") (pin "V10") (pinfunction "VCCINT_V10") (pintype "power_in"))
      (node (ref "IC39") (pin "V12") (pinfunction "VCCINT_V12") (pintype "power_in"))
    )
    (net (code "9") (name "VCC1P2") (class "Default")
      (node (ref "FR101") (pin "2") (pinfunction "2_2") (pintype "passive"))
    )
    (net (code "10") (name "VCC1P8") (class "Default")
      (node (ref "C462") (pin "2") (pinfunction "2_2") (pintype "passive"))
      (node (ref "C463") (pin "2") (pinfunction "2_2") (pintype "passive"))
      (node (ref "C464") (pin "1") (pinfunction "1_1") (pintype "passive"))
      (node (ref "C465") (pin "1") (pinfunction "1_1") (pintype "passive"))
      (node (ref "C466") (pin "1") (pinfunction "1_1") (pintype "passive"))
      (node (ref "C467") (pin "1") (pinfunction "1_1") (pintype "passive"))
      (node (ref "C468") (pin "1") (pinfunction "1_1") (pintype "passive"))
      (node (ref "FR102") (pin "1") (pinfunction "1_1") (pintype "passive"))
      (node (ref "IC39") (pin "J9") (pinfunction "VCCAUX_J9") (pintype "power_in"))
      (node (ref "IC39") (pin "L9") (pinfunction "VCCAUX_L9") (pintype "power_in"))
      (node (ref "IC39") (pin "N9") (pinfunction "VCCAUX_N9") (pintype "power_in"))
      (node (ref "IC39") (pin "R9") (pinfunction "VCCAUX_R9") (pintype "power_in"))
      (node (ref "IC39") (pin "U9") (pinfunction "VCCAUX_U9") (pintype "power_in"))
      (node (ref "R198") (pin "1") (pinfunction "1_1") (pintype "passive"))
    )
    (net (code "11") (name "VCC1P8_FADC") (class "Default")
      (node (ref "C500") (pin "2") (pinfunction "2_2") (pintype "passive"))
      (node (ref "C501") (pin "1") (pinfunction "1_1") (pintype "passive"))
      (node (ref "FR102") (pin "2") (pinfunction "2_2") (pintype "passive"))
      (node (ref "IC39") (pin "M12") (pinfunction "VCCADC_0_M12") (pintype "power_in"))
    )
    (net (code "12") (name "VCC2P5") (class "Default")
      (node (ref "C381") (pin "2") (pinfunction "2_2") (pintype "passive"))
      (node (ref "C382") (pin "2") (pinfunction "2_2") (pintype "passive"))
      (node (ref "C383") (pin "1") (pinfunction "1_1") (pintype "passive"))
      (node (ref "C384") (pin "1") (pinfunction "1_1") (pintype "passive"))
      (node (ref "C385") (pin "1") (pinfunction "1_1") (pintype "passive"))
      (node (ref "C386") (pin "1") (pinfunction "1_1") (pintype "passive"))
      (node (ref "C387") (pin "1") (pinfunction "1_1") (pintype "passive"))
      (node (ref "C388") (pin "1") (pinfunction "1_1") (pintype "passive"))
      (node (ref "C389") (pin "2") (pinfunction "2_2") (pintype "passive"))
      (node (ref "C390") (pin "2") (pinfunction "2_2") (pintype "passive"))
      (node (ref "C391") (pin "1") (pinfunction "1_1") (pintype "passive"))
      (node (ref "C392") (pin "1") (pinfunction "1_1") (pintype "passive"))
      (node (ref "C393") (pin "1") (pinfunction "1_1") (pintype "passive"))
      (node (ref "C394") (pin "1") (pinfunction "1_1") (pintype "passive"))
      (node (ref "C395") (pin "1") (pinfunction "1_1") (pintype "passive"))
      (node (ref "C396") (pin "1") (pinfunction "1_1") (pintype "passive"))
      (node (ref "C405") (pin "2") (pinfunction "2_2") (pintype "passive"))
      (node (ref "C406") (pin "2") (pinfunction "2_2") (pintype "passive"))
      (node (ref "C407") (pin "1") (pinfunction "1_1") (pintype "passive"))
      (node (ref "C408") (pin "1") (pinfunction "1_1") (pintype "passive"))
      (node (ref "C409") (pin "1") (pinfunction "1_1") (pintype "passive"))
      (node (ref "C410") (pin "1") (pinfunction "1_1") (pintype "passive"))
      (node (ref "C411") (pin "1") (pinfunction "1_1") (pintype "passive"))
      (node (ref "C412") (pin "1") (pinfunction "1_1") (pintype "passive"))
      (node (ref "C421") (pin "2") (pinfunction "2_2") (pintype "passive"))
      (node (ref "C422") (pin "2") (pinfunction "2_2") (pintype "passive"))
      (node (ref "C423") (pin "1") (pinfunction "1_1") (pintype "passive"))
      (node (ref "C424") (pin "1") (pinfunction "1_1") (pintype "passive"))
      (node (ref "C425") (pin "1") (pinfunction "1_1") (pintype "passive"))
      (node (ref "C426") (pin "1") (pinfunction "1_1") (pintype "passive"))
      (node (ref "C427") (pin "1") (pinfunction "1_1") (pintype "passive"))
      (node (ref "C428") (pin "1") (pinfunction "1_1") (pintype "passive"))
      (node (ref "C429") (pin "2") (pinfunction "2_2") (pintype "passive"))
      (node (ref "C430") (pin "2") (pinfunction "2_2") (pintype "passive"))
      (node (ref "C431") (pin "1") (pinfunction "1_1") (pintype "passive"))
      (node (ref "C432") (pin "1") (pinfunction "1_1") (pintype "passive"))
      (node (ref "C433") (pin "1") (pinfunction "1_1") (pintype "passive"))
      (node (ref "C434") (pin "1") (pinfunction "1_1") (pintype "passive"))
      (node (ref "C435") (pin "1") (pinfunction "1_1") (pintype "passive"))
      (node (ref "C436") (pin "1") (pinfunction "1_1") (pintype "passive"))
      (node (ref "C437") (pin "2") (pinfunction "2_2") (pintype "passive"))
      (node (ref "C438") (pin "2") (pinfunction "2_2") (pintype "passive"))
      (node (ref "C439") (pin "1") (pinfunction "1_1") (pintype "passive"))
      (node (ref "C440") (pin "1") (pinfunction "1_1") (pintype "passive"))
      (node (ref "C441") (pin "1") (pinfunction "1_1") (pintype "passive"))
      (node (ref "C442") (pin "1") (pinfunction "1_1") (pintype "passive"))
      (node (ref "C443") (pin "1") (pinfunction "1_1") (pintype "passive"))
      (node (ref "C444") (pin "1") (pinfunction "1_1") (pintype "passive"))
      (node (ref "IC39") (pin "A1") (pinfunction "VCCO_35_A1") (pintype "power_in"))
      (node (ref "IC39") (pin "A21") (pinfunction "VCCO_16_A21") (pintype "power_in"))
      (node (ref "IC39") (pin "AA21") (pinfunction "VCCO_12_AA21") (pintype "power_in"))
      (node (ref "IC39") (pin "AB18") (pinfunction "VCCO_12_AB18") (pintype "power_in"))
      (node (ref "IC39") (pin "AC25") (pinfunction "VCCO_13_AC25") (pintype "power_in"))
      (node (ref "IC39") (pin "AD22") (pinfunction "VCCO_12_AD22") (pintype "power_in"))
      (node (ref "IC39") (pin "AE19") (pinfunction "VCCO_12_AE19") (pintype "power_in"))
      (node (ref "IC39") (pin "AF26") (pinfunction "VCCO_12_AF26") (pintype "power_in"))
      (node (ref "IC39") (pin "B18") (pinfunction "VCCO_16_B18") (pintype "power_in"))
      (node (ref "IC39") (pin "C25") (pinfunction "VCCO_16_C25") (pintype "power_in"))
      (node (ref "IC39") (pin "C5") (pinfunction "VCCO_35_C5") (pintype "power_in"))
      (node (ref "IC39") (pin "D2") (pinfunction "VCCO_35_D2") (pintype "power_in"))
      (node (ref "IC39") (pin "D22") (pinfunction "VCCO_16_D22") (pintype "power_in"))
      (node (ref "IC39") (pin "E19") (pinfunction "VCCO_16_E19") (pintype "power_in"))
      (node (ref "IC39") (pin "F16") (pinfunction "VCCO_16_F16") (pintype "power_in"))
      (node (ref "IC39") (pin "F26") (pinfunction "VCCO_15_F26") (pintype "power_in"))
      (node (ref "IC39") (pin "F6") (pinfunction "VCCO_35_F6") (pintype "power_in"))
      (node (ref "IC39") (pin "G23") (pinfunction "VCCO_15_G23") (pintype "power_in"))
      (node (ref "IC39") (pin "G3") (pinfunction "VCCO_35_G3") (pintype "power_in"))
      (node (ref "IC39") (pin "H20") (pinfunction "VCCO_15_H20") (pintype "power_in"))
      (node (ref "IC39") (pin "J17") (pinfunction "VCCO_15_J17") (pintype "power_in"))
      (node (ref "IC39") (pin "J7") (pinfunction "VCCO_35_J7") (pintype "power_in"))
      (node (ref "IC39") (pin "K14") (pinfunction "VCCO_15_K14") (pintype "power_in"))
      (node (ref "IC39") (pin "K4") (pinfunction "VCCO_34_K4") (pintype "power_in"))
      (node (ref "IC39") (pin "L1") (pinfunction "VCCO_34_L1") (pintype "power_in"))
      (node (ref "IC39") (pin "M18") (pinfunction "VCCO_15_M18") (pintype "power_in"))
      (node (ref "IC39") (pin "M8") (pinfunction "VCCO_34_M8") (pintype "power_in"))
      (node (ref "IC39") (pin "N5") (pinfunction "VCCO_34_N5") (pintype "power_in"))
      (node (ref "IC39") (pin "P2") (pinfunction "VCCO_34_P2") (pintype "power_in"))
      (node (ref "IC39") (pin "T16") (pinfunction "VCCO_13_T16") (pintype "power_in"))
      (node (ref "IC39") (pin "T26") (pinfunction "VCCO_13_T26") (pintype "power_in"))
      (node (ref "IC39") (pin "T6") (pinfunction "VCCO_34_T6") (pintype "power_in"))
      (node (ref "IC39") (pin "U23") (pinfunction "VCCO_13_U23") (pintype "power_in"))
      (node (ref "IC39") (pin "V20") (pinfunction "VCCO_13_V20") (pintype "power_in"))
      (node (ref "IC39") (pin "W17") (pinfunction "VCCO_12_W17") (pintype "power_in"))
      (node (ref "IC39") (pin "Y24") (pinfunction "VCCO_13_Y24") (pintype "power_in"))
    )
    (net (code "13") (name "VCC3P3") (class "Default")
      (node (ref "C377") (pin "2") (pinfunction "2_2") (pintype "passive"))
      (node (ref "C378") (pin "2") (pinfunction "2_2") (pintype "passive"))
      (node (ref "C379") (pin "1") (pinfunction "1_1") (pintype "passive"))
      (node (ref "C380") (pin "1") (pinfunction "1_1") (pintype "passive"))
      (node (ref "C413") (pin "2") (pinfunction "2_2") (pintype "passive"))
      (node (ref "C414") (pin "2") (pinfunction "2_2") (pintype "passive"))
      (node (ref "C415") (pin "1") (pinfunction "1_1") (pintype "passive"))
      (node (ref "C416") (pin "1") (pinfunction "1_1") (pintype "passive"))
      (node (ref "C417") (pin "1") (pinfunction "1_1") (pintype "passive"))
      (node (ref "C418") (pin "1") (pinfunction "1_1") (pintype "passive"))
      (node (ref "C419") (pin "1") (pinfunction "1_1") (pintype "passive"))
      (node (ref "C420") (pin "1") (pinfunction "1_1") (pintype "passive"))
      (node (ref "IC39") (pin "K24") (pinfunction "VCCO_14_K24") (pintype "power_in"))
      (node (ref "IC39") (pin "L21") (pinfunction "VCCO_14_L21") (pintype "power_in"))
      (node (ref "IC39") (pin "N15") (pinfunction "VCCO_14_N15") (pintype "power_in"))
      (node (ref "IC39") (pin "N25") (pinfunction "VCCO_14_N25") (pintype "power_in"))
      (node (ref "IC39") (pin "P22") (pinfunction "VCCO_14_P22") (pintype "power_in"))
      (node (ref "IC39") (pin "R19") (pinfunction "VCCO_14_R19") (pintype "power_in"))
      (node (ref "IC39") (pin "W11") (pinfunction "VCCO_0_W11") (pintype "power_in"))
      (node (ref "IC39") (pin "Y14") (pinfunction "VCCO_0_Y14") (pintype "power_in"))
    )
    (net (code "14") (name "VDIO_LMS_FPGA") (class "Default")
      (node (ref "C397") (pin "2") (pinfunction "2_2") (pintype "passive"))
      (node (ref "C398") (pin "2") (pinfunction "2_2") (pintype "passive"))
      (node (ref "C399") (pin "1") (pinfunction "1_1") (pintype "passive"))
      (node (ref "C400") (pin "1") (pinfunction "1_1") (pintype "passive"))
      (node (ref "C401") (pin "1") (pinfunction "1_1") (pintype "passive"))
      (node (ref "C402") (pin "1") (pinfunction "1_1") (pintype "passive"))
      (node (ref "C403") (pin "1") (pinfunction "1_1") (pintype "passive"))
      (node (ref "C404") (pin "1") (pinfunction "1_1") (pintype "passive"))
      (node (ref "IC39") (pin "AA1") (pinfunction "VCCO_33_AA1") (pintype "power_in"))
      (node (ref "IC39") (pin "AC5") (pinfunction "VCCO_33_AC5") (pintype "power_in"))
      (node (ref "IC39") (pin "AD2") (pinfunction "VCCO_33_AD2") (pintype "power_in"))
      (node (ref "IC39") (pin "U3") (pinfunction "VCCO_33_U3") (pintype "power_in"))
      (node (ref "IC39") (pin "W7") (pinfunction "VCCO_33_W7") (pintype "power_in"))
      (node (ref "IC39") (pin "Y4") (pinfunction "VCCO_33_Y4") (pintype "power_in"))
    )
    (net (code "15") (name "unconnected-(BATT1-PadNEGATIVE)") (class "Default")
      (node (ref "BATT1") (pin "NEGATIVE") (pintype "passive+no_connect"))
    )
    (net (code "16") (name "unconnected-(BATT1-PadPOSITIVE)") (class "Default")
      (node (ref "BATT1") (pin "POSITIVE") (pintype "passive+no_connect"))
    )
  )
)
